# AugmentedStethoscope_v2.net
KiCad netlist of a schematic drawn in EAGLE
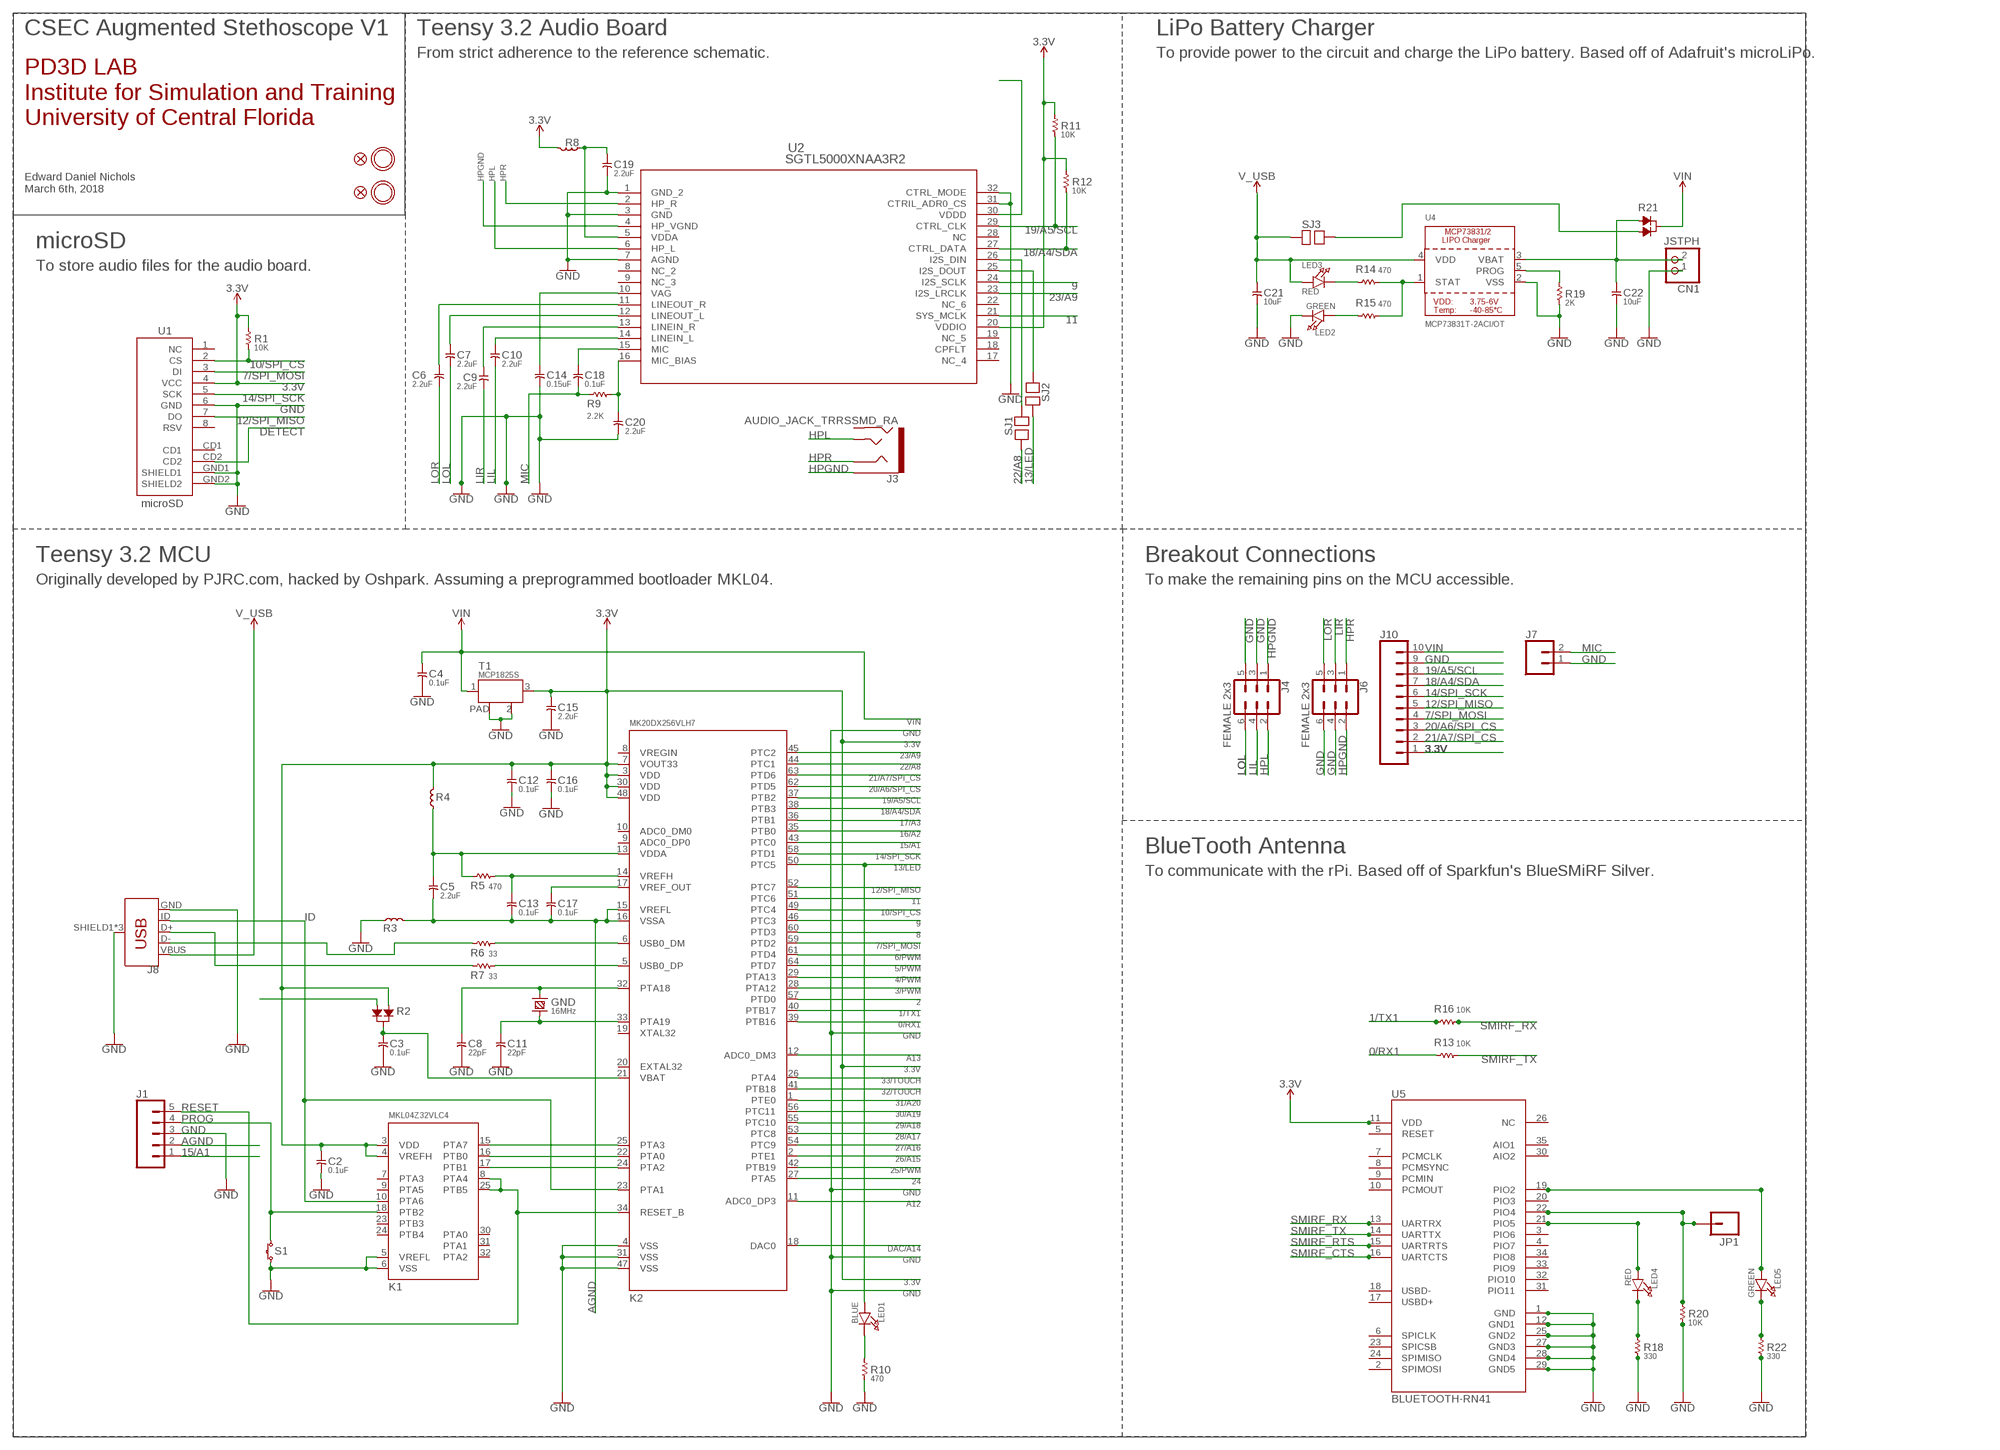
[diagram p0: schematic, sheet 1]

(export (version "E")
  (design (tool "Eeschema 10.0.6"))
  (components
    (comp (ref "C2")
      (value "0.1uF")
      (footprint "eagle-import:C0603")
      (fields (field (name "MF") "Murata Electronics") (field (name "MPN") "GRM188R71C104KA01D"))
      (libsource (lib "eagle-import") (part "CAPACITOR-0.1UF"))
    )
    (comp (ref "C3")
      (value "0.1uF")
      (footprint "eagle-import:C0603")
      (fields (field (name "MF") "Murata Electronics") (field (name "MPN") "GRM188R71C104KA01D"))
      (libsource (lib "eagle-import") (part "CAPACITOR-0.1UF"))
    )
    (comp (ref "C4")
      (value "0.1uF")
      (footprint "eagle-import:C0603")
      (fields (field (name "MF") "Murata Electronics") (field (name "MPN") "GRM188R71C104KA01D"))
      (libsource (lib "eagle-import") (part "CAPACITOR-0.1UF"))
    )
    (comp (ref "C5")
      (value "2.2uF")
      (footprint "eagle-import:C0805")
      (fields (field (name "MF") "Taiyo Yuden") (field (name "MPN") "TMK212B7225KG-TR"))
      (libsource (lib "eagle-import") (part "CAPACITOR-2.2UF"))
    )
    (comp (ref "C6")
      (value "2.2uF")
      (footprint "eagle-import:C0805")
      (fields (field (name "MF") "Taiyo Yuden") (field (name "MPN") "TMK212B7225KG-TR"))
      (libsource (lib "eagle-import") (part "CAPACITOR-2.2UF"))
    )
    (comp (ref "C7")
      (value "2.2uF")
      (footprint "eagle-import:C0805")
      (fields (field (name "MF") "Taiyo Yuden") (field (name "MPN") "TMK212B7225KG-TR"))
      (libsource (lib "eagle-import") (part "CAPACITOR-2.2UF"))
    )
    (comp (ref "C8")
      (value "22pF")
      (footprint "eagle-import:C0603")
      (fields (field (name "MF") "Vishay / Vitramon") (field (name "MPN") "VJ0603A220JXACW1BC"))
      (libsource (lib "eagle-import") (part "CAPACITOR-22PF"))
    )
    (comp (ref "C9")
      (value "2.2uF")
      (footprint "eagle-import:C0805")
      (fields (field (name "MF") "Taiyo Yuden") (field (name "MPN") "TMK212B7225KG-TR"))
      (libsource (lib "eagle-import") (part "CAPACITOR-2.2UF"))
    )
    (comp (ref "C10")
      (value "2.2uF")
      (footprint "eagle-import:C0805")
      (fields (field (name "MF") "Taiyo Yuden") (field (name "MPN") "TMK212B7225KG-TR"))
      (libsource (lib "eagle-import") (part "CAPACITOR-2.2UF"))
    )
    (comp (ref "C11")
      (value "22pF")
      (footprint "eagle-import:C0603")
      (fields (field (name "MF") "Vishay / Vitramon") (field (name "MPN") "VJ0603A220JXACW1BC"))
      (libsource (lib "eagle-import") (part "CAPACITOR-22PF"))
    )
    (comp (ref "C12")
      (value "0.1uF")
      (footprint "eagle-import:C0603")
      (fields (field (name "MF") "Murata Electronics") (field (name "MPN") "GRM188R71C104KA01D"))
      (libsource (lib "eagle-import") (part "CAPACITOR-0.1UF"))
    )
    (comp (ref "C13")
      (value "0.1uF")
      (footprint "eagle-import:C0603")
      (fields (field (name "MF") "Murata Electronics") (field (name "MPN") "GRM188R71C104KA01D"))
      (libsource (lib "eagle-import") (part "CAPACITOR-0.1UF"))
    )
    (comp (ref "C14")
      (value "0.15uF")
      (footprint "eagle-import:C0805")
      (fields (field (name "MF") "Taiyo Yuden") (field (name "MPN") "TMK212B7225KG-TR"))
      (libsource (lib "eagle-import") (part "CAPACITOR-2.2UF"))
    )
    (comp (ref "C15")
      (value "2.2uF")
      (footprint "eagle-import:C0805")
      (fields (field (name "MF") "Taiyo Yuden") (field (name "MPN") "TMK212B7225KG-TR"))
      (libsource (lib "eagle-import") (part "CAPACITOR-2.2UF"))
    )
    (comp (ref "C16")
      (value "0.1uF")
      (footprint "eagle-import:C0603")
      (fields (field (name "MF") "Murata Electronics") (field (name "MPN") "GRM188R71C104KA01D"))
      (libsource (lib "eagle-import") (part "CAPACITOR-0.1UF"))
    )
    (comp (ref "C17")
      (value "0.1uF")
      (footprint "eagle-import:C0603")
      (fields (field (name "MF") "Murata Electronics") (field (name "MPN") "GRM188R71C104KA01D"))
      (libsource (lib "eagle-import") (part "CAPACITOR-0.1UF"))
    )
    (comp (ref "C18")
      (value "0.1uF")
      (footprint "eagle-import:C0805")
      (fields (field (name "MF") "Taiyo Yuden") (field (name "MPN") "TMK212B7225KG-TR"))
      (libsource (lib "eagle-import") (part "CAPACITOR-2.2UF"))
    )
    (comp (ref "C19")
      (value "2.2uF")
      (footprint "eagle-import:C0805")
      (fields (field (name "MF") "Taiyo Yuden") (field (name "MPN") "TMK212B7225KG-TR"))
      (libsource (lib "eagle-import") (part "CAPACITOR-2.2UF"))
    )
    (comp (ref "C20")
      (value "2.2uF")
      (footprint "eagle-import:C0805")
      (fields (field (name "MF") "Taiyo Yuden") (field (name "MPN") "TMK212B7225KG-TR"))
      (libsource (lib "eagle-import") (part "CAPACITOR-2.2UF"))
    )
    (comp (ref "C21")
      (value "10uF")
      (footprint "eagle-import:C0603")
      (fields (field (name "MF") "Murata Electronics") (field (name "MPN") "GRM188R71C104KA01D"))
      (libsource (lib "eagle-import") (part "CAPACITOR-0.1UF"))
    )
    (comp (ref "C22")
      (value "10uF")
      (footprint "eagle-import:C0603")
      (fields (field (name "MF") "Murata Electronics") (field (name "MPN") "GRM188R71C104KA01D"))
      (libsource (lib "eagle-import") (part "CAPACITOR-0.1UF"))
    )
    (comp (ref "CN1")
      (value "JSTPH")
      (footprint "eagle-import:JSTPH2")
      (libsource (lib "eagle-import") (part "JST_2PIN"))
    )
    (comp (ref "FID2")
      (value "FIDUCIAL\"\"")
      (footprint "eagle-import:FIDUCIAL_1MM")
      (libsource (lib "eagle-import") (part "FIDUCIAL{dblquote}{dblquote}"))
    )
    (comp (ref "FID3")
      (value "FIDUCIAL\"\"")
      (footprint "eagle-import:FIDUCIAL_1MM")
      (fields (field (name "BOM") "EXCLUDE"))
      (libsource (lib "eagle-import") (part "FIDUCIAL{dblquote}{dblquote}"))
    )
    (comp (ref "GND")
      (value "16MHz")
      (footprint "eagle-import:HC49US")
      (fields (field (name "MF") "ABRACON") (field (name "MPN") "ABL-16.000MHz-B1U"))
      (libsource (lib "eagle-import") (part "CRYSTAL-HC49US"))
    )
    (comp (ref "J1")
      (value "CONN_05")
      (footprint "eagle-import:1X05")
      (libsource (lib "eagle-import") (part "CONN_05"))
    )
    (comp (ref "J3")
      (value "AUDIO_JACK_TRRSSMD_RA")
      (footprint "eagle-import:AUDIO_JACK_3.5MM_TRRS_SMD_RA")
      (libsource (lib "eagle-import") (part "AUDIO_JACK_TRRSSMD_RA"))
    )
    (comp (ref "J4")
      (value "FEMALE 2x3")
      (footprint "eagle-import:2X3")
      (libsource (lib "eagle-import") (part "CONN_03X2FEMALE"))
    )
    (comp (ref "J6")
      (value "FEMALE 2x3")
      (footprint "eagle-import:2X3")
      (libsource (lib "eagle-import") (part "CONN_03X2FEMALE"))
    )
    (comp (ref "J7")
      (value "CONN_02")
      (footprint "eagle-import:1X02")
      (libsource (lib "eagle-import") (part "CONN_02"))
    )
    (comp (ref "J8")
      (value "USB_MICRO-B_FEMALE-SMT")
      (footprint "eagle-import:USB-B-MICRO-SMD")
      (libsource (lib "eagle-import") (part "USB_MICRO-B_FEMALE-SMT"))
    )
    (comp (ref "J10")
      (value "CONN_10\"")
      (footprint "eagle-import:1X10")
      (libsource (lib "eagle-import") (part "CONN_10{dblquote}"))
    )
    (comp (ref "JP1")
      (value "M01SMDNS")
      (footprint "eagle-import:1X01NS")
      (libsource (lib "eagle-import") (part "M01SMDNS"))
    )
    (comp (ref "K1")
      (value "MKL04Z32VLC4")
      (footprint "eagle-import:LQFP32-08")
      (fields (field (name "MF") "PJRC") (field (name "MPN") "IC_MKL04Z32_TQFP32"))
      (libsource (lib "eagle-import") (part "MKL04Z32VLC4"))
    )
    (comp (ref "K2")
      (value "MK20DX256VLH7")
      (footprint "eagle-import:LQFP64-05")
      (fields (field (name "MF") "NXP"))
      (libsource (lib "eagle-import") (part "MK20DX256VLH7"))
    )
    (comp (ref "LED1")
      (value "BLUE")
      (footprint "eagle-import:CHIPLED_0805")
      (libsource (lib "eagle-import") (part "LED0805"))
    )
    (comp (ref "LED2")
      (value "GREEN")
      (footprint "eagle-import:CHIPLED_0805")
      (libsource (lib "eagle-import") (part "LED0805"))
    )
    (comp (ref "LED3")
      (value "RED")
      (footprint "eagle-import:CHIPLED_0805")
      (libsource (lib "eagle-import") (part "LED0805"))
    )
    (comp (ref "LED4")
      (value "RED")
      (footprint "eagle-import:CHIPLED_0805")
      (libsource (lib "eagle-import") (part "LED0805"))
    )
    (comp (ref "LED5")
      (value "GREEN")
      (footprint "eagle-import:CHIPLED_0805")
      (libsource (lib "eagle-import") (part "LED0805"))
    )
    (comp (ref "R1")
      (value "10K")
      (footprint "eagle-import:R0603")
      (fields (field (name "MF") "Vishay") (field (name "MPN") "CRCW0603470RFKEA"))
      (libsource (lib "eagle-import") (part "RESISTOR-470R"))
    )
    (comp (ref "R2")
      (value "DIODE_DUAL")
      (footprint "eagle-import:SOT-23")
      (fields (field (name "MF") "NXP Semiconductors") (field (name "MPN") "BAT54C,215"))
      (libsource (lib "eagle-import") (part "DIODE_DUAL"))
    )
    (comp (ref "R3")
      (value "FERRITE")
      (footprint "eagle-import:L0603")
      (fields (field (name "MF") "Murata Electronics") (field (name "MPN") " BLM18AG601SN1D"))
      (libsource (lib "eagle-import") (part "FERRITE"))
    )
    (comp (ref "R4")
      (value "FERRITE")
      (footprint "eagle-import:L0603")
      (fields (field (name "MF") "Murata Electronics") (field (name "MPN") " BLM18AG601SN1D"))
      (libsource (lib "eagle-import") (part "FERRITE"))
    )
    (comp (ref "R5")
      (value "470")
      (footprint "eagle-import:R0603")
      (fields (field (name "MF") "Vishay") (field (name "MPN") "CRCW0603470RFKEA"))
      (libsource (lib "eagle-import") (part "RESISTOR-470R"))
    )
    (comp (ref "R6")
      (value "33")
      (footprint "eagle-import:R0603")
      (fields (field (name "MF") "Panasonic") (field (name "MPN") "ERJ-PA3F33R0V"))
      (libsource (lib "eagle-import") (part "RESISTOR-33R"))
    )
    (comp (ref "R7")
      (value "33")
      (footprint "eagle-import:R0603")
      (fields (field (name "MF") "Panasonic") (field (name "MPN") "ERJ-PA3F33R0V"))
      (libsource (lib "eagle-import") (part "RESISTOR-33R"))
    )
    (comp (ref "R8")
      (value "FERRITE")
      (footprint "eagle-import:L0603")
      (fields (field (name "MF") "Murata Electronics") (field (name "MPN") " BLM18AG601SN1D"))
      (libsource (lib "eagle-import") (part "FERRITE"))
    )
    (comp (ref "R9")
      (value "2.2K")
      (footprint "eagle-import:R0603")
      (fields (field (name "MF") "Vishay") (field (name "MPN") "CRCW0603470RFKEA"))
      (libsource (lib "eagle-import") (part "RESISTOR-470R"))
    )
    (comp (ref "R10")
      (value "470")
      (footprint "eagle-import:R0603")
      (fields (field (name "MF") "Vishay") (field (name "MPN") "CRCW0603470RFKEA"))
      (libsource (lib "eagle-import") (part "RESISTOR-470R"))
    )
    (comp (ref "R11")
      (value "10K")
      (footprint "eagle-import:R0603")
      (fields (field (name "MF") "Vishay") (field (name "MPN") "CRCW0603470RFKEA"))
      (libsource (lib "eagle-import") (part "RESISTOR-470R"))
    )
    (comp (ref "R12")
      (value "10K")
      (footprint "eagle-import:R0603")
      (fields (field (name "MF") "Vishay") (field (name "MPN") "CRCW0603470RFKEA"))
      (libsource (lib "eagle-import") (part "RESISTOR-470R"))
    )
    (comp (ref "R13")
      (value "10K")
      (footprint "eagle-import:R0603")
      (fields (field (name "MF") "Panasonic") (field (name "MPN") "ERJ-PA3F33R0V"))
      (libsource (lib "eagle-import") (part "RESISTOR-33R"))
    )
    (comp (ref "R14")
      (value "470")
      (footprint "eagle-import:R0603")
      (fields (field (name "MF") "Panasonic") (field (name "MPN") "ERJ-PA3F33R0V"))
      (libsource (lib "eagle-import") (part "RESISTOR-33R"))
    )
    (comp (ref "R15")
      (value "470")
      (footprint "eagle-import:R0603")
      (fields (field (name "MF") "Panasonic") (field (name "MPN") "ERJ-PA3F33R0V"))
      (libsource (lib "eagle-import") (part "RESISTOR-33R"))
    )
    (comp (ref "R16")
      (value "10K")
      (footprint "eagle-import:R0603")
      (fields (field (name "MF") "Panasonic") (field (name "MPN") "ERJ-PA3F33R0V"))
      (libsource (lib "eagle-import") (part "RESISTOR-33R"))
    )
    (comp (ref "R18")
      (value "330")
      (footprint "eagle-import:R0603")
      (fields (field (name "MF") "Vishay") (field (name "MPN") "CRCW0603470RFKEA"))
      (libsource (lib "eagle-import") (part "RESISTOR-470R"))
    )
    (comp (ref "R19")
      (value "2K")
      (footprint "eagle-import:R0603")
      (fields (field (name "MF") "Vishay") (field (name "MPN") "CRCW0603470RFKEA"))
      (libsource (lib "eagle-import") (part "RESISTOR-470R"))
    )
    (comp (ref "R20")
      (value "10K")
      (footprint "eagle-import:R0603")
      (fields (field (name "MF") "Vishay") (field (name "MPN") "CRCW0603470RFKEA"))
      (libsource (lib "eagle-import") (part "RESISTOR-470R"))
    )
    (comp (ref "R21")
      (value "DIODE_DUAL")
      (footprint "eagle-import:SOT-23")
      (fields (field (name "MF") "NXP Semiconductors") (field (name "MPN") "BAT54C,215"))
      (libsource (lib "eagle-import") (part "DIODE_DUAL"))
    )
    (comp (ref "R22")
      (value "330")
      (footprint "eagle-import:R0603")
      (fields (field (name "MF") "Vishay") (field (name "MPN") "CRCW0603470RFKEA"))
      (libsource (lib "eagle-import") (part "RESISTOR-470R"))
    )
    (comp (ref "S1")
      (value "TACT_SWITCH")
      (footprint "eagle-import:ALPS_SKHH")
      (fields (field (name "MF") "ALPS") (field (name "MPN") "SKHHPKA010"))
      (libsource (lib "eagle-import") (part "TACT_SWITCH"))
    )
    (comp (ref "SJ1")
      (value "SOLDERJUMPER")
      (footprint "eagle-import:SOLDERJUMPER")
      (libsource (lib "eagle-import") (part "SOLDERJUMPER"))
    )
    (comp (ref "SJ2")
      (value "SOLDERJUMPER")
      (footprint "eagle-import:SOLDERJUMPER")
      (libsource (lib "eagle-import") (part "SOLDERJUMPER"))
    )
    (comp (ref "SJ3")
      (value "SOLDERJUMPER")
      (footprint "eagle-import:SOLDERJUMPER")
      (libsource (lib "eagle-import") (part "SOLDERJUMPER"))
    )
    (comp (ref "T1")
      (value "MCP1825S")
      (footprint "eagle-import:SOT-223")
      (fields (field (name "MF") "Microchip Technology") (field (name "MPN") "MCP1825S-3302E/DB"))
      (libsource (lib "eagle-import") (part "LDO"))
    )
    (comp (ref "U$1")
      (value "MOUNTINGHOLE2.5")
      (footprint "eagle-import:MOUNTINGHOLE_2.5_PLATED")
      (libsource (lib "eagle-import") (part "MOUNTINGHOLE2.5"))
    )
    (comp (ref "U$15")
      (value "MOUNTINGHOLE2.5")
      (footprint "eagle-import:MOUNTINGHOLE_2.5_PLATED")
      (libsource (lib "eagle-import") (part "MOUNTINGHOLE2.5"))
    )
    (comp (ref "U1")
      (value "microSD")
      (footprint "eagle-import:MICRO-SD-SOCKET-PP")
      (libsource (lib "eagle-import") (part "USD-SOCKETSMD"))
    )
    (comp (ref "U2")
      (value "SGTL5000XNAA3R2")
      (footprint "eagle-import:QFN32")
      (libsource (lib "eagle-import") (part "SGTL5000XNAA3R2"))
    )
    (comp (ref "U4")
      (value "MCP73831T-2ACI/OT")
      (footprint "eagle-import:SOT23-5")
      (libsource (lib "eagle-import") (part "MCP73831/2"))
    )
    (comp (ref "U5")
      (value "BLUETOOTH-RN41")
      (footprint "eagle-import:RN41")
      (libsource (lib "eagle-import") (part "BLUETOOTH-RN41{dblquote}"))
    )
  )
  (nets
    (net (code "1") (name "/0{slash}RX1") (class "Default")
      (node (ref "K2") (pin "39") (pinfunction "PTB16_39") (pintype "bidirectional"))
      (node (ref "R13") (pin "1") (pinfunction "1_1") (pintype "passive"))
    )
    (net (code "2") (name "/1{slash}TX1") (class "Default")
      (node (ref "K2") (pin "40") (pinfunction "PTB17_40") (pintype "bidirectional"))
      (node (ref "R16") (pin "1") (pinfunction "1_1") (pintype "passive"))
    )
    (net (code "3") (name "/2") (class "Default")
      (node (ref "K2") (pin "57") (pinfunction "PTD0_57") (pintype "bidirectional"))
    )
    (net (code "4") (name "/3{slash}PWM") (class "Default")
      (node (ref "K2") (pin "28") (pinfunction "PTA12_28") (pintype "bidirectional"))
    )
    (net (code "5") (name "/4{slash}PWM") (class "Default")
      (node (ref "K2") (pin "29") (pinfunction "PTA13_29") (pintype "bidirectional"))
    )
    (net (code "6") (name "/5{slash}PWM") (class "Default")
      (node (ref "K2") (pin "64") (pinfunction "PTD7_64") (pintype "bidirectional"))
    )
    (net (code "7") (name "/6{slash}PWM") (class "Default")
      (node (ref "K2") (pin "61") (pinfunction "PTD4_61") (pintype "bidirectional"))
    )
    (net (code "8") (name "/7{slash}SPI_MOSI") (class "Default")
      (node (ref "J10") (pin "4") (pinfunction "4_4") (pintype "passive"))
      (node (ref "K2") (pin "59") (pinfunction "PTD2_59") (pintype "bidirectional"))
      (node (ref "U1") (pin "3") (pinfunction "DI_3") (pintype "bidirectional"))
    )
    (net (code "9") (name "/8") (class "Default")
      (node (ref "K2") (pin "60") (pinfunction "PTD3_60") (pintype "bidirectional"))
    )
    (net (code "10") (name "/9") (class "Default")
      (node (ref "K2") (pin "46") (pinfunction "PTC3_46") (pintype "bidirectional"))
      (node (ref "U2") (pin "24") (pinfunction "I2S_SCLK_24") (pintype "passive"))
    )
    (net (code "11") (name "/10{slash}SPI_CS") (class "Default")
      (node (ref "K2") (pin "49") (pinfunction "PTC4_49") (pintype "bidirectional"))
      (node (ref "R1") (pin "1") (pinfunction "1_1") (pintype "passive"))
      (node (ref "U1") (pin "2") (pinfunction "CS_2") (pintype "bidirectional"))
    )
    (net (code "12") (name "/11") (class "Default")
      (node (ref "K2") (pin "51") (pinfunction "PTC6_51") (pintype "bidirectional"))
      (node (ref "U2") (pin "21") (pinfunction "SYS_MCLK_21") (pintype "passive"))
    )
    (net (code "13") (name "/12{slash}SPI_MISO") (class "Default")
      (node (ref "J10") (pin "5") (pinfunction "5_5") (pintype "passive"))
      (node (ref "K2") (pin "52") (pinfunction "PTC7_52") (pintype "bidirectional"))
      (node (ref "U1") (pin "7") (pinfunction "DO_7") (pintype "bidirectional"))
    )
    (net (code "14") (name "/13{slash}LED") (class "Default")
      (node (ref "K2") (pin "50") (pinfunction "PTC5_50") (pintype "bidirectional"))
      (node (ref "LED1") (pin "A") (pinfunction "A_A") (pintype "passive"))
      (node (ref "SJ2") (pin "2") (pinfunction "2_2") (pintype "passive"))
    )
    (net (code "15") (name "/14{slash}SPI_SCK") (class "Default")
      (node (ref "J10") (pin "6") (pinfunction "6_6") (pintype "passive"))
      (node (ref "K2") (pin "58") (pinfunction "PTD1_58") (pintype "bidirectional"))
      (node (ref "U1") (pin "5") (pinfunction "SCK_5") (pintype "bidirectional"))
    )
    (net (code "16") (name "/15{slash}A1") (class "Default")
      (node (ref "J1") (pin "1") (pinfunction "1_1") (pintype "passive"))
      (node (ref "K2") (pin "43") (pinfunction "PTC0_43") (pintype "bidirectional"))
    )
    (net (code "17") (name "/16{slash}A2") (class "Default")
      (node (ref "K2") (pin "35") (pinfunction "PTB0_35") (pintype "bidirectional"))
    )
    (net (code "18") (name "/17{slash}A3") (class "Default")
      (node (ref "K2") (pin "36") (pinfunction "PTB1_36") (pintype "bidirectional"))
    )
    (net (code "19") (name "/18{slash}A4{slash}SDA") (class "Default")
      (node (ref "J10") (pin "7") (pinfunction "7_7") (pintype "passive"))
      (node (ref "K2") (pin "38") (pinfunction "PTB3_38") (pintype "bidirectional"))
      (node (ref "R12") (pin "1") (pinfunction "1_1") (pintype "passive"))
      (node (ref "U2") (pin "27") (pinfunction "CTRL_DATA_27") (pintype "passive"))
    )
    (net (code "20") (name "/19{slash}A5{slash}SCL") (class "Default")
      (node (ref "J10") (pin "8") (pinfunction "8_8") (pintype "passive"))
      (node (ref "K2") (pin "37") (pinfunction "PTB2_37") (pintype "bidirectional"))
      (node (ref "R11") (pin "1") (pinfunction "1_1") (pintype "passive"))
      (node (ref "U2") (pin "29") (pinfunction "CTRL_CLK_29") (pintype "passive"))
    )
    (net (code "21") (name "/20{slash}A6{slash}SPI_CS") (class "Default")
      (node (ref "J10") (pin "3") (pinfunction "3_3") (pintype "passive"))
      (node (ref "K2") (pin "62") (pinfunction "PTD5_62") (pintype "bidirectional"))
    )
    (net (code "22") (name "/21{slash}A7{slash}SPI_CS") (class "Default")
      (node (ref "J10") (pin "2") (pinfunction "2_2") (pintype "passive"))
      (node (ref "K2") (pin "63") (pinfunction "PTD6_63") (pintype "bidirectional"))
    )
    (net (code "23") (name "/22{slash}A8") (class "Default")
      (node (ref "K2") (pin "44") (pinfunction "PTC1_44") (pintype "bidirectional"))
      (node (ref "SJ1") (pin "2") (pinfunction "2_2") (pintype "passive"))
    )
    (net (code "24") (name "/23{slash}A9") (class "Default")
      (node (ref "K2") (pin "45") (pinfunction "PTC2_45") (pintype "bidirectional"))
      (node (ref "U2") (pin "23") (pinfunction "I2S_LRCLK_23") (pintype "passive"))
    )
    (net (code "25") (name "/24") (class "Default")
      (node (ref "K2") (pin "27") (pinfunction "PTA5_27") (pintype "bidirectional"))
    )
    (net (code "26") (name "/25{slash}PWM") (class "Default")
      (node (ref "K2") (pin "42") (pinfunction "PTB19_42") (pintype "bidirectional"))
    )
    (net (code "27") (name "/26{slash}A15") (class "Default")
      (node (ref "K2") (pin "2") (pinfunction "PTE1_2") (pintype "bidirectional"))
    )
    (net (code "28") (name "/27{slash}A16") (class "Default")
      (node (ref "K2") (pin "54") (pinfunction "PTC9_54") (pintype "bidirectional"))
    )
    (net (code "29") (name "/28{slash}A17") (class "Default")
      (node (ref "K2") (pin "53") (pinfunction "PTC8_53") (pintype "bidirectional"))
    )
    (net (code "30") (name "/29{slash}A18") (class "Default")
      (node (ref "K2") (pin "55") (pinfunction "PTC10_55") (pintype "bidirectional"))
    )
    (net (code "31") (name "/30{slash}A19") (class "Default")
      (node (ref "K2") (pin "56") (pinfunction "PTC11_56") (pintype "bidirectional"))
    )
    (net (code "32") (name "/31{slash}A20") (class "Default")
      (node (ref "K2") (pin "1") (pinfunction "PTE0_1") (pintype "bidirectional"))
    )
    (net (code "33") (name "/32{slash}TOUCH") (class "Default")
      (node (ref "K2") (pin "41") (pinfunction "PTB18_41") (pintype "bidirectional"))
    )
    (net (code "34") (name "/33{slash}TOUCH") (class "Default")
      (node (ref "K2") (pin "26") (pinfunction "PTA4_26") (pintype "bidirectional"))
    )
    (net (code "35") (name "/A12") (class "Default")
      (node (ref "K2") (pin "11") (pinfunction "ADC0_DP3_11") (pintype "bidirectional"))
    )
    (net (code "36") (name "/A13") (class "Default")
      (node (ref "K2") (pin "12") (pinfunction "ADC0_DM3_12") (pintype "bidirectional"))
    )
    (net (code "37") (name "/AGND") (class "Default")
      (node (ref "C13") (pin "2") (pinfunction "2_2") (pintype "passive"))
      (node (ref "C17") (pin "2") (pinfunction "2_2") (pintype "passive"))
      (node (ref "C5") (pin "2") (pinfunction "2_2") (pintype "passive"))
      (node (ref "J1") (pin "2") (pinfunction "2_2") (pintype "passive"))
      (node (ref "K2") (pin "15") (pinfunction "VREFL_15") (pintype "bidirectional"))
      (node (ref "K2") (pin "16") (pinfunction "VSSA_16") (pintype "bidirectional"))
      (node (ref "R3") (pin "2") (pinfunction "2_2") (pintype "passive"))
    )
    (net (code "38") (name "/DAC{slash}A14") (class "Default")
      (node (ref "K2") (pin "18") (pinfunction "DAC0_18") (pintype "bidirectional"))
    )
    (net (code "39") (name "/DETECT") (class "Default")
      (node (ref "U1") (pin "CD2") (pinfunction "CD2_CD2") (pintype "bidirectional"))
    )
    (net (code "40") (name "/HPGND") (class "Default")
      (node (ref "J3") (pin "EARTH") (pinfunction "EARTH_EARTH") (pintype "bidirectional"))
      (node (ref "J4") (pin "1") (pinfunction "1_1") (pintype "bidirectional"))
      (node (ref "J6") (pin "2") (pinfunction "2_2") (pintype "bidirectional"))
      (node (ref "U2") (pin "4") (pinfunction "HP_VGND_4") (pintype "power_in"))
    )
    (net (code "41") (name "/HPL") (class "Default")
      (node (ref "J3") (pin "TIP") (pinfunction "TIP_TIP") (pintype "bidirectional"))
      (node (ref "J4") (pin "2") (pinfunction "2_2") (pintype "bidirectional"))
      (node (ref "U2") (pin "6") (pinfunction "HP_L_6") (pintype "output"))
    )
    (net (code "42") (name "/HPR") (class "Default")
      (node (ref "J3") (pin "RING1") (pinfunction "RING1_RING1") (pintype "bidirectional"))
      (node (ref "J6") (pin "1") (pinfunction "1_1") (pintype "bidirectional"))
      (node (ref "U2") (pin "2") (pinfunction "HP_R_2") (pintype "output"))
    )
    (net (code "43") (name "/ID") (class "Default")
      (node (ref "J8") (pin "ID") (pinfunction "ID_ID") (pintype "bidirectional"))
      (node (ref "K1") (pin "10") (pinfunction "PTA6_10") (pintype "bidirectional"))
      (node (ref "K2") (pin "23") (pinfunction "PTA1_23") (pintype "bidirectional"))
    )
    (net (code "44") (name "/LIL") (class "Default")
      (node (ref "C10") (pin "2") (pinfunction "2_2") (pintype "passive"))
      (node (ref "J4") (pin "4") (pinfunction "4_4") (pintype "bidirectional"))
    )
    (net (code "45") (name "/LIR") (class "Default")
      (node (ref "C9") (pin "2") (pinfunction "2_2") (pintype "passive"))
      (node (ref "J6") (pin "3") (pinfunction "3_3") (pintype "bidirectional"))
    )
    (net (code "46") (name "/LOL") (class "Default")
      (node (ref "C7") (pin "2") (pinfunction "2_2") (pintype "passive"))
      (node (ref "J4") (pin "6") (pinfunction "6_6") (pintype "bidirectional"))
    )
    (net (code "47") (name "/LOR") (class "Default")
      (node (ref "C6") (pin "2") (pinfunction "2_2") (pintype "passive"))
      (node (ref "J6") (pin "5") (pinfunction "5_5") (pintype "bidirectional"))
    )
    (net (code "48") (name "/MIC") (class "Default")
      (node (ref "C18") (pin "2") (pinfunction "2_2") (pintype "passive"))
      (node (ref "J7") (pin "2") (pinfunction "2_2") (pintype "passive"))
      (node (ref "R9") (pin "1") (pinfunction "1_1") (pintype "passive"))
    )
    (net (code "49") (name "/PROG") (class "Default")
      (node (ref "J1") (pin "4") (pinfunction "4_4") (pintype "passive"))
      (node (ref "K1") (pin "18") (pinfunction "PTB2_18") (pintype "bidirectional"))
      (node (ref "S1") (pin "1") (pinfunction "1_1") (pintype "passive"))
      (node (ref "S1") (pin "2") (pinfunction "1_2") (pintype "passive"))
    )
    (net (code "50") (name "/RESET") (class "Default")
      (node (ref "J1") (pin "5") (pinfunction "5_5") (pintype "passive"))
      (node (ref "K1") (pin "25") (pinfunction "PTB5_25") (pintype "bidirectional"))
      (node (ref "K1") (pin "8") (pinfunction "PTA4_8") (pintype "bidirectional"))
      (node (ref "K2") (pin "34") (pinfunction "RESET_B_34") (pintype "bidirectional"))
    )
    (net (code "51") (name "/SMIRF_CTS") (class "Default")
      (node (ref "U5") (pin "16") (pinfunction "UARTCTS_16") (pintype "bidirectional"))
    )
    (net (code "52") (name "/SMIRF_RTS") (class "Default")
      (node (ref "U5") (pin "15") (pinfunction "UARTRTS_15") (pintype "bidirectional"))
    )
    (net (code "53") (name "/SMIRF_RX") (class "Default")
      (node (ref "R16") (pin "2") (pinfunction "2_2") (pintype "passive"))
      (node (ref "U5") (pin "13") (pinfunction "UARTRX_13") (pintype "bidirectional"))
    )
    (net (code "54") (name "/SMIRF_TX") (class "Default")
      (node (ref "R13") (pin "2") (pinfunction "2_2") (pintype "passive"))
      (node (ref "U5") (pin "14") (pinfunction "UARTTX_14") (pintype "bidirectional"))
    )
    (net (code "55") (name "3.3V") (class "Default")
      (node (ref "C12") (pin "1") (pinfunction "1_1") (pintype "passive"))
      (node (ref "C15") (pin "1") (pinfunction "1_1") (pintype "passive"))
      (node (ref "C16") (pin "1") (pinfunction "1_1") (pintype "passive"))
      (node (ref "C2") (pin "1") (pinfunction "1_1") (pintype "passive"))
      (node (ref "J10") (pin "1") (pinfunction "1_1") (pintype "passive"))
      (node (ref "K1") (pin "3") (pinfunction "VDD_3") (pintype "bidirectional"))
      (node (ref "K1") (pin "4") (pinfunction "VREFH_4") (pintype "bidirectional"))
      (node (ref "K2") (pin "3") (pinfunction "VDD_3") (pintype "bidirectional"))
      (node (ref "K2") (pin "30") (pinfunction "VDD_30") (pintype "bidirectional"))
      (node (ref "K2") (pin "48") (pinfunction "VDD_48") (pintype "bidirectional"))
      (node (ref "K2") (pin "7") (pinfunction "VOUT33_7") (pintype "bidirectional"))
      (node (ref "R1") (pin "2") (pinfunction "2_2") (pintype "passive"))
      (node (ref "R11") (pin "2") (pinfunction "2_2") (pintype "passive"))
      (node (ref "R12") (pin "2") (pinfunction "2_2") (pintype "passive"))
      (node (ref "R2") (pin "1") (pinfunction "1_1") (pintype "bidirectional"))
      (node (ref "R4") (pin "2") (pinfunction "2_2") (pintype "passive"))
      (node (ref "R8") (pin "2") (pinfunction "2_2") (pintype "passive"))
      (node (ref "T1") (pin "3") (pinfunction "OUT_3") (pintype "bidirectional"))
      (node (ref "U1") (pin "4") (pinfunction "VCC_4") (pintype "bidirectional"))
      (node (ref "U2") (pin "20") (pinfunction "VDDIO_20") (pintype "power_in"))
      (node (ref "U5") (pin "11") (pinfunction "VDD_11") (pintype "bidirectional"))
    )
    (net (code "56") (name "GND") (class "Default")
      (node (ref "C11") (pin "2") (pinfunction "2_2") (pintype "passive"))
      (node (ref "C12") (pin "2") (pinfunction "2_2") (pintype "passive"))
      (node (ref "C14") (pin "2") (pinfunction "2_2") (pintype "passive"))
      (node (ref "C15") (pin "2") (pinfunction "2_2") (pintype "passive"))
      (node (ref "C16") (pin "2") (pinfunction "2_2") (pintype "passive"))
      (node (ref "C19") (pin "2") (pinfunction "2_2") (pintype "passive"))
      (node (ref "C2") (pin "2") (pinfunction "2_2") (pintype "passive"))
      (node (ref "C20") (pin "2") (pinfunction "2_2") (pintype "passive"))
      (node (ref "C21") (pin "2") (pinfunction "2_2") (pintype "passive"))
      (node (ref "C22") (pin "2") (pinfunction "2_2") (pintype "passive"))
      (node (ref "C3") (pin "2") (pinfunction "2_2") (pintype "passive"))
      (node (ref "C4") (pin "2") (pinfunction "2_2") (pintype "passive"))
      (node (ref "C8") (pin "2") (pinfunction "2_2") (pintype "passive"))
      (node (ref "CN1") (pin "1") (pinfunction "1_1") (pintype "passive"))
      (node (ref "J1") (pin "3") (pinfunction "3_3") (pintype "passive"))
      (node (ref "J10") (pin "9") (pinfunction "9_9") (pintype "passive"))
      (node (ref "J4") (pin "3") (pinfunction "3_3") (pintype "bidirectional"))
      (node (ref "J4") (pin "5") (pinfunction "5_5") (pintype "bidirectional"))
      (node (ref "J6") (pin "4") (pinfunction "4_4") (pintype "bidirectional"))
      (node (ref "J6") (pin "6") (pinfunction "6_6") (pintype "bidirectional"))
      (node (ref "J7") (pin "1") (pinfunction "1_1") (pintype "passive"))
      (node (ref "J8") (pin "GND") (pinfunction "GND_GND") (pintype "power_in"))
      (node (ref "J8") (pin "SHIELD1") (pinfunction "SHIELD_SHIELD1") (pintype "bidirectional"))
      (node (ref "J8") (pin "SHIELD2") (pinfunction "SHIELD_SHIELD2") (pintype "bidirectional"))
      (node (ref "J8") (pin "SHIELD3") (pinfunction "SHIELD_SHIELD3") (pintype "bidirectional"))
      (node (ref "K1") (pin "5") (pinfunction "VREFL_5") (pintype "bidirectional"))
      (node (ref "K1") (pin "6") (pinfunction "VSS_6") (pintype "bidirectional"))
      (node (ref "K2") (pin "31") (pinfunction "VSS_31") (pintype "bidirectional"))
      (node (ref "K2") (pin "4") (pinfunction "VSS_4") (pintype "bidirectional"))
      (node (ref "K2") (pin "47") (pinfunction "VSS_47") (pintype "bidirectional"))
      (node (ref "LED2") (pin "C") (pinfunction "C_C") (pintype "passive"))
      (node (ref "R10") (pin "1") (pinfunction "1_1") (pintype "passive"))
      (node (ref "R18") (pin "1") (pinfunction "1_1") (pintype "passive"))
      (node (ref "R19") (pin "1") (pinfunction "1_1") (pintype "passive"))
      (node (ref "R20") (pin "1") (pinfunction "1_1") (pintype "passive"))
      (node (ref "R22") (pin "1") (pinfunction "1_1") (pintype "passive"))
      (node (ref "R3") (pin "1") (pinfunction "1_1") (pintype "passive"))
      (node (ref "S1") (pin "3") (pinfunction "3_3") (pintype "passive"))
      (node (ref "S1") (pin "4") (pinfunction "3_4") (pintype "passive"))
      (node (ref "T1") (pin "2") (pinfunction "GND_2") (pintype "bidirectional"))
      (node (ref "T1") (pin "PAD") (pinfunction "PAD_PAD") (pintype "bidirectional"))
      (node (ref "U1") (pin "6") (pinfunction "GND_6") (pintype "bidirectional"))
      (node (ref "U1") (pin "GND1") (pinfunction "SHIELD1_GND1") (pintype "bidirectional"))
      (node (ref "U1") (pin "GND2") (pinfunction "SHIELD2_GND2") (pintype "bidirectional"))
      (node (ref "U2") (pin "1") (pinfunction "GND_2_1") (pintype "power_in"))
      (node (ref "U2") (pin "3") (pinfunction "GND_3") (pintype "power_in"))
      (node (ref "U2") (pin "31") (pinfunction "CTRIL_ADR0_CS_31") (pintype "passive"))
      (node (ref "U2") (pin "32") (pinfunction "CTRL_MODE_32") (pintype "passive"))
      (node (ref "U2") (pin "7") (pinfunction "AGND_7") (pintype "power_in"))
      (node (ref "U4") (pin "2") (pinfunction "VSS_2") (pintype "power_in"))
      (node (ref "U5") (pin "1") (pinfunction "GND_1") (pintype "bidirectional"))
      (node (ref "U5") (pin "12") (pinfunction "GND1_12") (pintype "bidirectional"))
      (node (ref "U5") (pin "25") (pinfunction "GND2_25") (pintype "bidirectional"))
      (node (ref "U5") (pin "27") (pinfunction "GND3_27") (pintype "bidirectional"))
      (node (ref "U5") (pin "28") (pinfunction "GND4_28") (pintype "bidirectional"))
      (node (ref "U5") (pin "29") (pinfunction "GND5_29") (pintype "bidirectional"))
    )
    (net (code "57") (name "Net-(J8-PadD+)") (class "Default")
      (node (ref "J8") (pin "D+") (pinfunction "D+_D+") (pintype "bidirectional"))
      (node (ref "R7") (pin "1") (pinfunction "1_1") (pintype "passive"))
    )
    (net (code "58") (name "Net-(J8-PadD-)") (class "Default")
      (node (ref "J8") (pin "D-") (pinfunction "D-_D-") (pintype "bidirectional"))
      (node (ref "R6") (pin "1") (pinfunction "1_1") (pintype "passive"))
    )
    (net (code "59") (name "Net-(K1-PTA7)") (class "Default")
      (node (ref "K1") (pin "15") (pinfunction "PTA7_15") (pintype "bidirectional"))
      (node (ref "K2") (pin "25") (pinfunction "PTA3_25") (pintype "bidirectional"))
    )
    (net (code "60") (name "Net-(K1-PTB0)") (class "Default")
      (node (ref "K1") (pin "16") (pinfunction "PTB0_16") (pintype "bidirectional"))
      (node (ref "K2") (pin "22") (pinfunction "PTA0_22") (pintype "bidirectional"))
    )
    (net (code "61") (name "Net-(K1-PTB1)") (class "Default")
      (node (ref "K1") (pin "17") (pinfunction "PTB1_17") (pintype "bidirectional"))
      (node (ref "K2") (pin "24") (pinfunction "PTA2_24") (pintype "bidirectional"))
    )
    (net (code "62") (name "Net-(K2-PTA18)") (class "Default")
      (node (ref "C8") (pin "1") (pinfunction "1_1") (pintype "passive"))
      (node (ref "GND") (pin "1") (pinfunction "1_1") (pintype "passive"))
      (node (ref "K2") (pin "32") (pinfunction "PTA18_32") (pintype "bidirectional"))
    )
    (net (code "63") (name "Net-(K2-PTA19)") (class "Default")
      (node (ref "C11") (pin "1") (pinfunction "1_1") (pintype "passive"))
      (node (ref "GND") (pin "2") (pinfunction "2_2") (pintype "passive"))
      (node (ref "K2") (pin "33") (pinfunction "PTA19_33") (pintype "bidirectional"))
    )
    (net (code "64") (name "Net-(K2-USB0_DM)") (class "Default")
      (node (ref "K2") (pin "6") (pinfunction "USB0_DM_6") (pintype "bidirectional"))
      (node (ref "R6") (pin "2") (pinfunction "2_2") (pintype "passive"))
    )
    (net (code "65") (name "Net-(K2-USB0_DP)") (class "Default")
      (node (ref "K2") (pin "5") (pinfunction "USB0_DP_5") (pintype "bidirectional"))
      (node (ref "R7") (pin "2") (pinfunction "2_2") (pintype "passive"))
    )
    (net (code "66") (name "Net-(K2-VBAT)") (class "Default")
      (node (ref "C3") (pin "1") (pinfunction "1_1") (pintype "passive"))
      (node (ref "K2") (pin "21") (pinfunction "VBAT_21") (pintype "bidirectional"))
      (node (ref "R2") (pin "3") (pinfunction "3_3") (pintype "bidirectional"))
    )
    (net (code "67") (name "Net-(K2-VDDA)") (class "Default")
      (node (ref "C5") (pin "1") (pinfunction "1_1") (pintype "passive"))
      (node (ref "K2") (pin "13") (pinfunction "VDDA_13") (pintype "bidirectional"))
      (node (ref "R4") (pin "1") (pinfunction "1_1") (pintype "passive"))
      (node (ref "R5") (pin "1") (pinfunction "1_1") (pintype "passive"))
    )
    (net (code "68") (name "Net-(K2-VREFH)") (class "Default")
      (node (ref "C13") (pin "1") (pinfunction "1_1") (pintype "passive"))
      (node (ref "K2") (pin "14") (pinfunction "VREFH_14") (pintype "bidirectional"))
      (node (ref "R5") (pin "2") (pinfunction "2_2") (pintype "passive"))
    )
    (net (code "69") (name "Net-(K2-VREF_OUT)") (class "Default")
      (node (ref "C17") (pin "1") (pinfunction "1_1") (pintype "passive"))
      (node (ref "K2") (pin "17") (pinfunction "VREF_OUT_17") (pintype "bidirectional"))
    )
    (net (code "70") (name "Net-(LED1-PadC)") (class "Default")
      (node (ref "LED1") (pin "C") (pinfunction "C_C") (pintype "passive"))
      (node (ref "R10") (pin "2") (pinfunction "2_2") (pintype "passive"))
    )
    (net (code "71") (name "Net-(LED2-PadA)") (class "Default")
      (node (ref "LED2") (pin "A") (pinfunction "A_A") (pintype "passive"))
      (node (ref "R15") (pin "1") (pinfunction "1_1") (pintype "passive"))
    )
    (net (code "72") (name "Net-(LED3-PadC)") (class "Default")
      (node (ref "LED3") (pin "C") (pinfunction "C_C") (pintype "passive"))
      (node (ref "R14") (pin "1") (pinfunction "1_1") (pintype "passive"))
    )
    (net (code "73") (name "Net-(LED4-PadC)") (class "Default")
      (node (ref "LED4") (pin "C") (pinfunction "C_C") (pintype "passive"))
      (node (ref "R18") (pin "2") (pinfunction "2_2") (pintype "passive"))
    )
    (net (code "74") (name "Net-(LED5-PadC)") (class "Default")
      (node (ref "LED5") (pin "C") (pinfunction "C_C") (pintype "passive"))
      (node (ref "R22") (pin "2") (pinfunction "2_2") (pintype "passive"))
    )
    (net (code "75") (name "Net-(R21-Pad2)") (class "Default")
      (node (ref "R21") (pin "2") (pinfunction "2_2") (pintype "bidirectional"))
      (node (ref "SJ3") (pin "2") (pinfunction "2_2") (pintype "passive"))
    )
    (net (code "76") (name "Net-(U2-I2S_DIN)") (class "Default")
      (node (ref "SJ1") (pin "1") (pinfunction "1_1") (pintype "passive"))
      (node (ref "U2") (pin "26") (pinfunction "I2S_DIN_26") (pintype "input"))
    )
    (net (code "77") (name "Net-(U2-I2S_DOUT)") (class "Default")
      (node (ref "SJ2") (pin "1") (pinfunction "1_1") (pintype "passive"))
      (node (ref "U2") (pin "25") (pinfunction "I2S_DOUT_25") (pintype "output"))
    )
    (net (code "78") (name "Net-(U2-LINEIN_L)") (class "Default")
      (node (ref "C10") (pin "1") (pinfunction "1_1") (pintype "passive"))
      (node (ref "U2") (pin "14") (pinfunction "LINEIN_L_14") (pintype "input"))
    )
    (net (code "79") (name "Net-(U2-LINEIN_R)") (class "Default")
      (node (ref "C9") (pin "1") (pinfunction "1_1") (pintype "passive"))
      (node (ref "U2") (pin "13") (pinfunction "LINEIN_R_13") (pintype "input"))
    )
    (net (code "80") (name "Net-(U2-LINEOUT_L)") (class "Default")
      (node (ref "C7") (pin "1") (pinfunction "1_1") (pintype "passive"))
      (node (ref "U2") (pin "12") (pinfunction "LINEOUT_L_12") (pintype "output"))
    )
    (net (code "81") (name "Net-(U2-LINEOUT_R)") (class "Default")
      (node (ref "C6") (pin "1") (pinfunction "1_1") (pintype "passive"))
      (node (ref "U2") (pin "11") (pinfunction "LINEOUT_R_11") (pintype "output"))
    )
    (net (code "82") (name "Net-(U2-MIC)") (class "Default")
      (node (ref "C18") (pin "1") (pinfunction "1_1") (pintype "passive"))
      (node (ref "U2") (pin "15") (pinfunction "MIC_15") (pintype "input"))
    )
    (net (code "83") (name "Net-(U2-MIC_BIAS)") (class "Default")
      (node (ref "C20") (pin "1") (pinfunction "1_1") (pintype "passive"))
      (node (ref "R9") (pin "2") (pinfunction "2_2") (pintype "passive"))
      (node (ref "U2") (pin "16") (pinfunction "MIC_BIAS_16") (pintype "passive"))
    )
    (net (code "84") (name "Net-(U2-VAG)") (class "Default")
      (node (ref "C14") (pin "1") (pinfunction "1_1") (pintype "passive"))
      (node (ref "U2") (pin "10") (pinfunction "VAG_10") (pintype "passive"))
    )
    (net (code "85") (name "Net-(U2-VDDA)") (class "Default")
      (node (ref "C19") (pin "1") (pinfunction "1_1") (pintype "passive"))
      (node (ref "R8") (pin "1") (pinfunction "1_1") (pintype "passive"))
      (node (ref "U2") (pin "5") (pinfunction "VDDA_5") (pintype "power_in"))
    )
    (net (code "86") (name "Net-(U4-PROG)") (class "Default")
      (node (ref "R19") (pin "2") (pinfunction "2_2") (pintype "passive"))
      (node (ref "U4") (pin "5") (pinfunction "PROG_5") (pintype "input"))
    )
    (net (code "87") (name "Net-(U4-STAT)") (class "Default")
      (node (ref "R14") (pin "2") (pinfunction "2_2") (pintype "passive"))
      (node (ref "R15") (pin "2") (pinfunction "2_2") (pintype "passive"))
      (node (ref "U4") (pin "1") (pinfunction "STAT_1") (pintype "output"))
    )
    (net (code "88") (name "Net-(U4-VBAT)") (class "Default")
      (node (ref "C22") (pin "1") (pinfunction "1_1") (pintype "passive"))
      (node (ref "CN1") (pin "2") (pinfunction "2_2") (pintype "passive"))
      (node (ref "R21") (pin "1") (pinfunction "1_1") (pintype "bidirectional"))
      (node (ref "U4") (pin "3") (pinfunction "VBAT_3") (pintype "power_in"))
    )
    (net (code "89") (name "Net-(U5-PIO2)") (class "Default")
      (node (ref "LED5") (pin "A") (pinfunction "A_A") (pintype "passive"))
      (node (ref "U5") (pin "19") (pinfunction "PIO2_19") (pintype "bidirectional"))
    )
    (net (code "90") (name "Net-(U5-PIO4)") (class "Default")
      (node (ref "JP1") (pin "1") (pinfunction "1_1") (pintype "passive"))
      (node (ref "R20") (pin "2") (pinfunction "2_2") (pintype "passive"))
      (node (ref "U5") (pin "22") (pinfunction "PIO4_22") (pintype "bidirectional"))
    )
    (net (code "91") (name "Net-(U5-PIO5)") (class "Default")
      (node (ref "LED4") (pin "A") (pinfunction "A_A") (pintype "passive"))
      (node (ref "U5") (pin "21") (pinfunction "PIO5_21") (pintype "bidirectional"))
    )
    (net (code "92") (name "VIN") (class "Default")
      (node (ref "C4") (pin "1") (pinfunction "1_1") (pintype "passive"))
      (node (ref "J10") (pin "10") (pinfunction "10_10") (pintype "passive"))
      (node (ref "R21") (pin "3") (pinfunction "3_3") (pintype "bidirectional"))
      (node (ref "T1") (pin "1") (pinfunction "IN_1") (pintype "bidirectional"))
    )
    (net (code "93") (name "V_USB") (class "Default")
      (node (ref "C21") (pin "1") (pinfunction "1_1") (pintype "passive"))
      (node (ref "J8") (pin "VBUS") (pinfunction "VBUS_VBUS") (pintype "power_in"))
      (node (ref "LED3") (pin "A") (pinfunction "A_A") (pintype "passive"))
      (node (ref "SJ3") (pin "1") (pinfunction "1_1") (pintype "passive"))
      (node (ref "U4") (pin "4") (pinfunction "VDD_4") (pintype "power_in"))
    )
    (net (code "94") (name "unconnected-(J3-PadRING2)") (class "Default")
      (node (ref "J3") (pin "RING2") (pinfunction "RING2_RING2") (pintype "bidirectional"))
    )
    (net (code "95") (name "unconnected-(K1-PTA0-Pad30)") (class "Default")
      (node (ref "K1") (pin "30") (pinfunction "PTA0_30") (pintype "bidirectional"))
    )
    (net (code "96") (name "unconnected-(K1-PTA1-Pad31)") (class "Default")
      (node (ref "K1") (pin "31") (pinfunction "PTA1_31") (pintype "bidirectional"))
    )
    (net (code "97") (name "unconnected-(K1-PTA2-Pad32)") (class "Default")
      (node (ref "K1") (pin "32") (pinfunction "PTA2_32") (pintype "bidirectional"))
    )
    (net (code "98") (name "unconnected-(K1-PTA3-Pad7)") (class "Default")
      (node (ref "K1") (pin "7") (pinfunction "PTA3_7") (pintype "bidirectional"))
    )
    (net (code "99") (name "unconnected-(K1-PTA5-Pad9)") (class "Default")
      (node (ref "K1") (pin "9") (pinfunction "PTA5_9") (pintype "bidirectional"))
    )
    (net (code "100") (name "unconnected-(K1-PTB3-Pad23)") (class "Default")
      (node (ref "K1") (pin "23") (pinfunction "PTB3_23") (pintype "bidirectional"))
    )
    (net (code "101") (name "unconnected-(K1-PTB4-Pad24)") (class "Default")
      (node (ref "K1") (pin "24") (pinfunction "PTB4_24") (pintype "bidirectional"))
    )
    (net (code "102") (name "unconnected-(K2-ADC0_DM0-Pad10)") (class "Default")
      (node (ref "K2") (pin "10") (pinfunction "ADC0_DM0_10") (pintype "bidirectional"))
    )
    (net (code "103") (name "unconnected-(K2-ADC0_DP0-Pad9)") (class "Default")
      (node (ref "K2") (pin "9") (pinfunction "ADC0_DP0_9") (pintype "bidirectional"))
    )
    (net (code "104") (name "unconnected-(K2-EXTAL32-Pad20)") (class "Default")
      (node (ref "K2") (pin "20") (pinfunction "EXTAL32_20") (pintype "bidirectional"))
    )
    (net (code "105") (name "unconnected-(K2-VREGIN-Pad8)") (class "Default")
      (node (ref "K2") (pin "8") (pinfunction "VREGIN_8") (pintype "bidirectional"))
    )
    (net (code "106") (name "unconnected-(K2-XTAL32-Pad19)") (class "Default")
      (node (ref "K2") (pin "19") (pinfunction "XTAL32_19") (pintype "bidirectional"))
    )
    (net (code "107") (name "unconnected-(R2-Pad2)") (class "Default")
      (node (ref "R2") (pin "2") (pinfunction "2_2") (pintype "bidirectional"))
    )
    (net (code "108") (name "unconnected-(U1-NC-Pad1)") (class "Default")
      (node (ref "U1") (pin "1") (pinfunction "NC_1") (pintype "bidirectional"))
    )
    (net (code "109") (name "unconnected-(U1-PadCD1)") (class "Default")
      (node (ref "U1") (pin "CD1") (pinfunction "CD1_CD1") (pintype "bidirectional"))
    )
    (net (code "110") (name "unconnected-(U1-RSV-Pad8)") (class "Default")
      (node (ref "U1") (pin "8") (pinfunction "RSV_8") (pintype "bidirectional"))
    )
    (net (code "111") (name "unconnected-(U2-CPFLT-Pad18)") (class "Default")
      (node (ref "U2") (pin "18") (pinfunction "CPFLT_18") (pintype "passive"))
    )
    (net (code "112") (name "unconnected-(U2-NC-Pad28)") (class "Default")
      (node (ref "U2") (pin "28") (pinfunction "NC_28") (pintype "passive"))
    )
    (net (code "113") (name "unconnected-(U2-NC_2-Pad8)") (class "Default")
      (node (ref "U2") (pin "8") (pinfunction "NC_2_8") (pintype "passive"))
    )
    (net (code "114") (name "unconnected-(U2-NC_3-Pad9)") (class "Default")
      (node (ref "U2") (pin "9") (pinfunction "NC_3_9") (pintype "passive"))
    )
    (net (code "115") (name "unconnected-(U2-NC_4-Pad17)") (class "Default")
      (node (ref "U2") (pin "17") (pinfunction "NC_4_17") (pintype "passive"))
    )
    (net (code "116") (name "unconnected-(U2-NC_5-Pad19)") (class "Default")
      (node (ref "U2") (pin "19") (pinfunction "NC_5_19") (pintype "passive"))
    )
    (net (code "117") (name "unconnected-(U2-NC_6-Pad22)") (class "Default")
      (node (ref "U2") (pin "22") (pinfunction "NC_6_22") (pintype "passive"))
    )
    (net (code "118") (name "unconnected-(U2-VDDD-Pad30)") (class "Default")
      (node (ref "U2") (pin "30") (pinfunction "VDDD_30") (pintype "power_in"))
    )
    (net (code "119") (name "unconnected-(U5-AIO1-Pad35)") (class "Default")
      (node (ref "U5") (pin "35") (pinfunction "AIO1_35") (pintype "bidirectional"))
    )
    (net (code "120") (name "unconnected-(U5-AIO2-Pad30)") (class "Default")
      (node (ref "U5") (pin "30") (pinfunction "AIO2_30") (pintype "bidirectional"))
    )
    (net (code "121") (name "unconnected-(U5-NC-Pad26)") (class "Default")
      (node (ref "U5") (pin "26") (pinfunction "NC_26") (pintype "bidirectional"))
    )
    (net (code "122") (name "unconnected-(U5-PCMCLK-Pad7)") (class "Default")
      (node (ref "U5") (pin "7") (pinfunction "PCMCLK_7") (pintype "bidirectional"))
    )
    (net (code "123") (name "unconnected-(U5-PCMIN-Pad9)") (class "Default")
      (node (ref "U5") (pin "9") (pinfunction "PCMIN_9") (pintype "bidirectional"))
    )
    (net (code "124") (name "unconnected-(U5-PCMOUT-Pad10)") (class "Default")
      (node (ref "U5") (pin "10") (pinfunction "PCMOUT_10") (pintype "bidirectional"))
    )
    (net (code "125") (name "unconnected-(U5-PCMSYNC-Pad8)") (class "Default")
      (node (ref "U5") (pin "8") (pinfunction "PCMSYNC_8") (pintype "bidirectional"))
    )
    (net (code "126") (name "unconnected-(U5-PIO3-Pad20)") (class "Default")
      (node (ref "U5") (pin "20") (pinfunction "PIO3_20") (pintype "bidirectional"))
    )
    (net (code "127") (name "unconnected-(U5-PIO6-Pad3)") (class "Default")
      (node (ref "U5") (pin "3") (pinfunction "PIO6_3") (pintype "bidirectional"))
    )
    (net (code "128") (name "unconnected-(U5-PIO7-Pad4)") (class "Default")
      (node (ref "U5") (pin "4") (pinfunction "PIO7_4") (pintype "bidirectional"))
    )
    (net (code "129") (name "unconnected-(U5-PIO8-Pad34)") (class "Default")
      (node (ref "U5") (pin "34") (pinfunction "PIO8_34") (pintype "bidirectional"))
    )
    (net (code "130") (name "unconnected-(U5-PIO9-Pad33)") (class "Default")
      (node (ref "U5") (pin "33") (pinfunction "PIO9_33") (pintype "bidirectional"))
    )
    (net (code "131") (name "unconnected-(U5-PIO10-Pad32)") (class "Default")
      (node (ref "U5") (pin "32") (pinfunction "PIO10_32") (pintype "bidirectional"))
    )
    (net (code "132") (name "unconnected-(U5-PIO11-Pad31)") (class "Default")
      (node (ref "U5") (pin "31") (pinfunction "PIO11_31") (pintype "bidirectional"))
    )
    (net (code "133") (name "unconnected-(U5-RESET-Pad5)") (class "Default")
      (node (ref "U5") (pin "5") (pinfunction "RESET_5") (pintype "bidirectional"))
    )
    (net (code "134") (name "unconnected-(U5-SPICLK-Pad6)") (class "Default")
      (node (ref "U5") (pin "6") (pinfunction "SPICLK_6") (pintype "bidirectional"))
    )
    (net (code "135") (name "unconnected-(U5-SPICSB-Pad23)") (class "Default")
      (node (ref "U5") (pin "23") (pinfunction "SPICSB_23") (pintype "bidirectional"))
    )
    (net (code "136") (name "unconnected-(U5-SPIMISO-Pad24)") (class "Default")
      (node (ref "U5") (pin "24") (pinfunction "SPIMISO_24") (pintype "bidirectional"))
    )
    (net (code "137") (name "unconnected-(U5-SPIMOSI-Pad2)") (class "Default")
      (node (ref "U5") (pin "2") (pinfunction "SPIMOSI_2") (pintype "bidirectional"))
    )
    (net (code "138") (name "unconnected-(U5-USBD+-Pad17)") (class "Default")
      (node (ref "U5") (pin "17") (pinfunction "USBD+_17") (pintype "bidirectional"))
    )
    (net (code "139") (name "unconnected-(U5-USBD--Pad18)") (class "Default")
      (node (ref "U5") (pin "18") (pinfunction "USBD-_18") (pintype "bidirectional"))
    )
  )
)
